# ProPrj.net
KiCad netlist of a schematic drawn in EasyEDA Pro
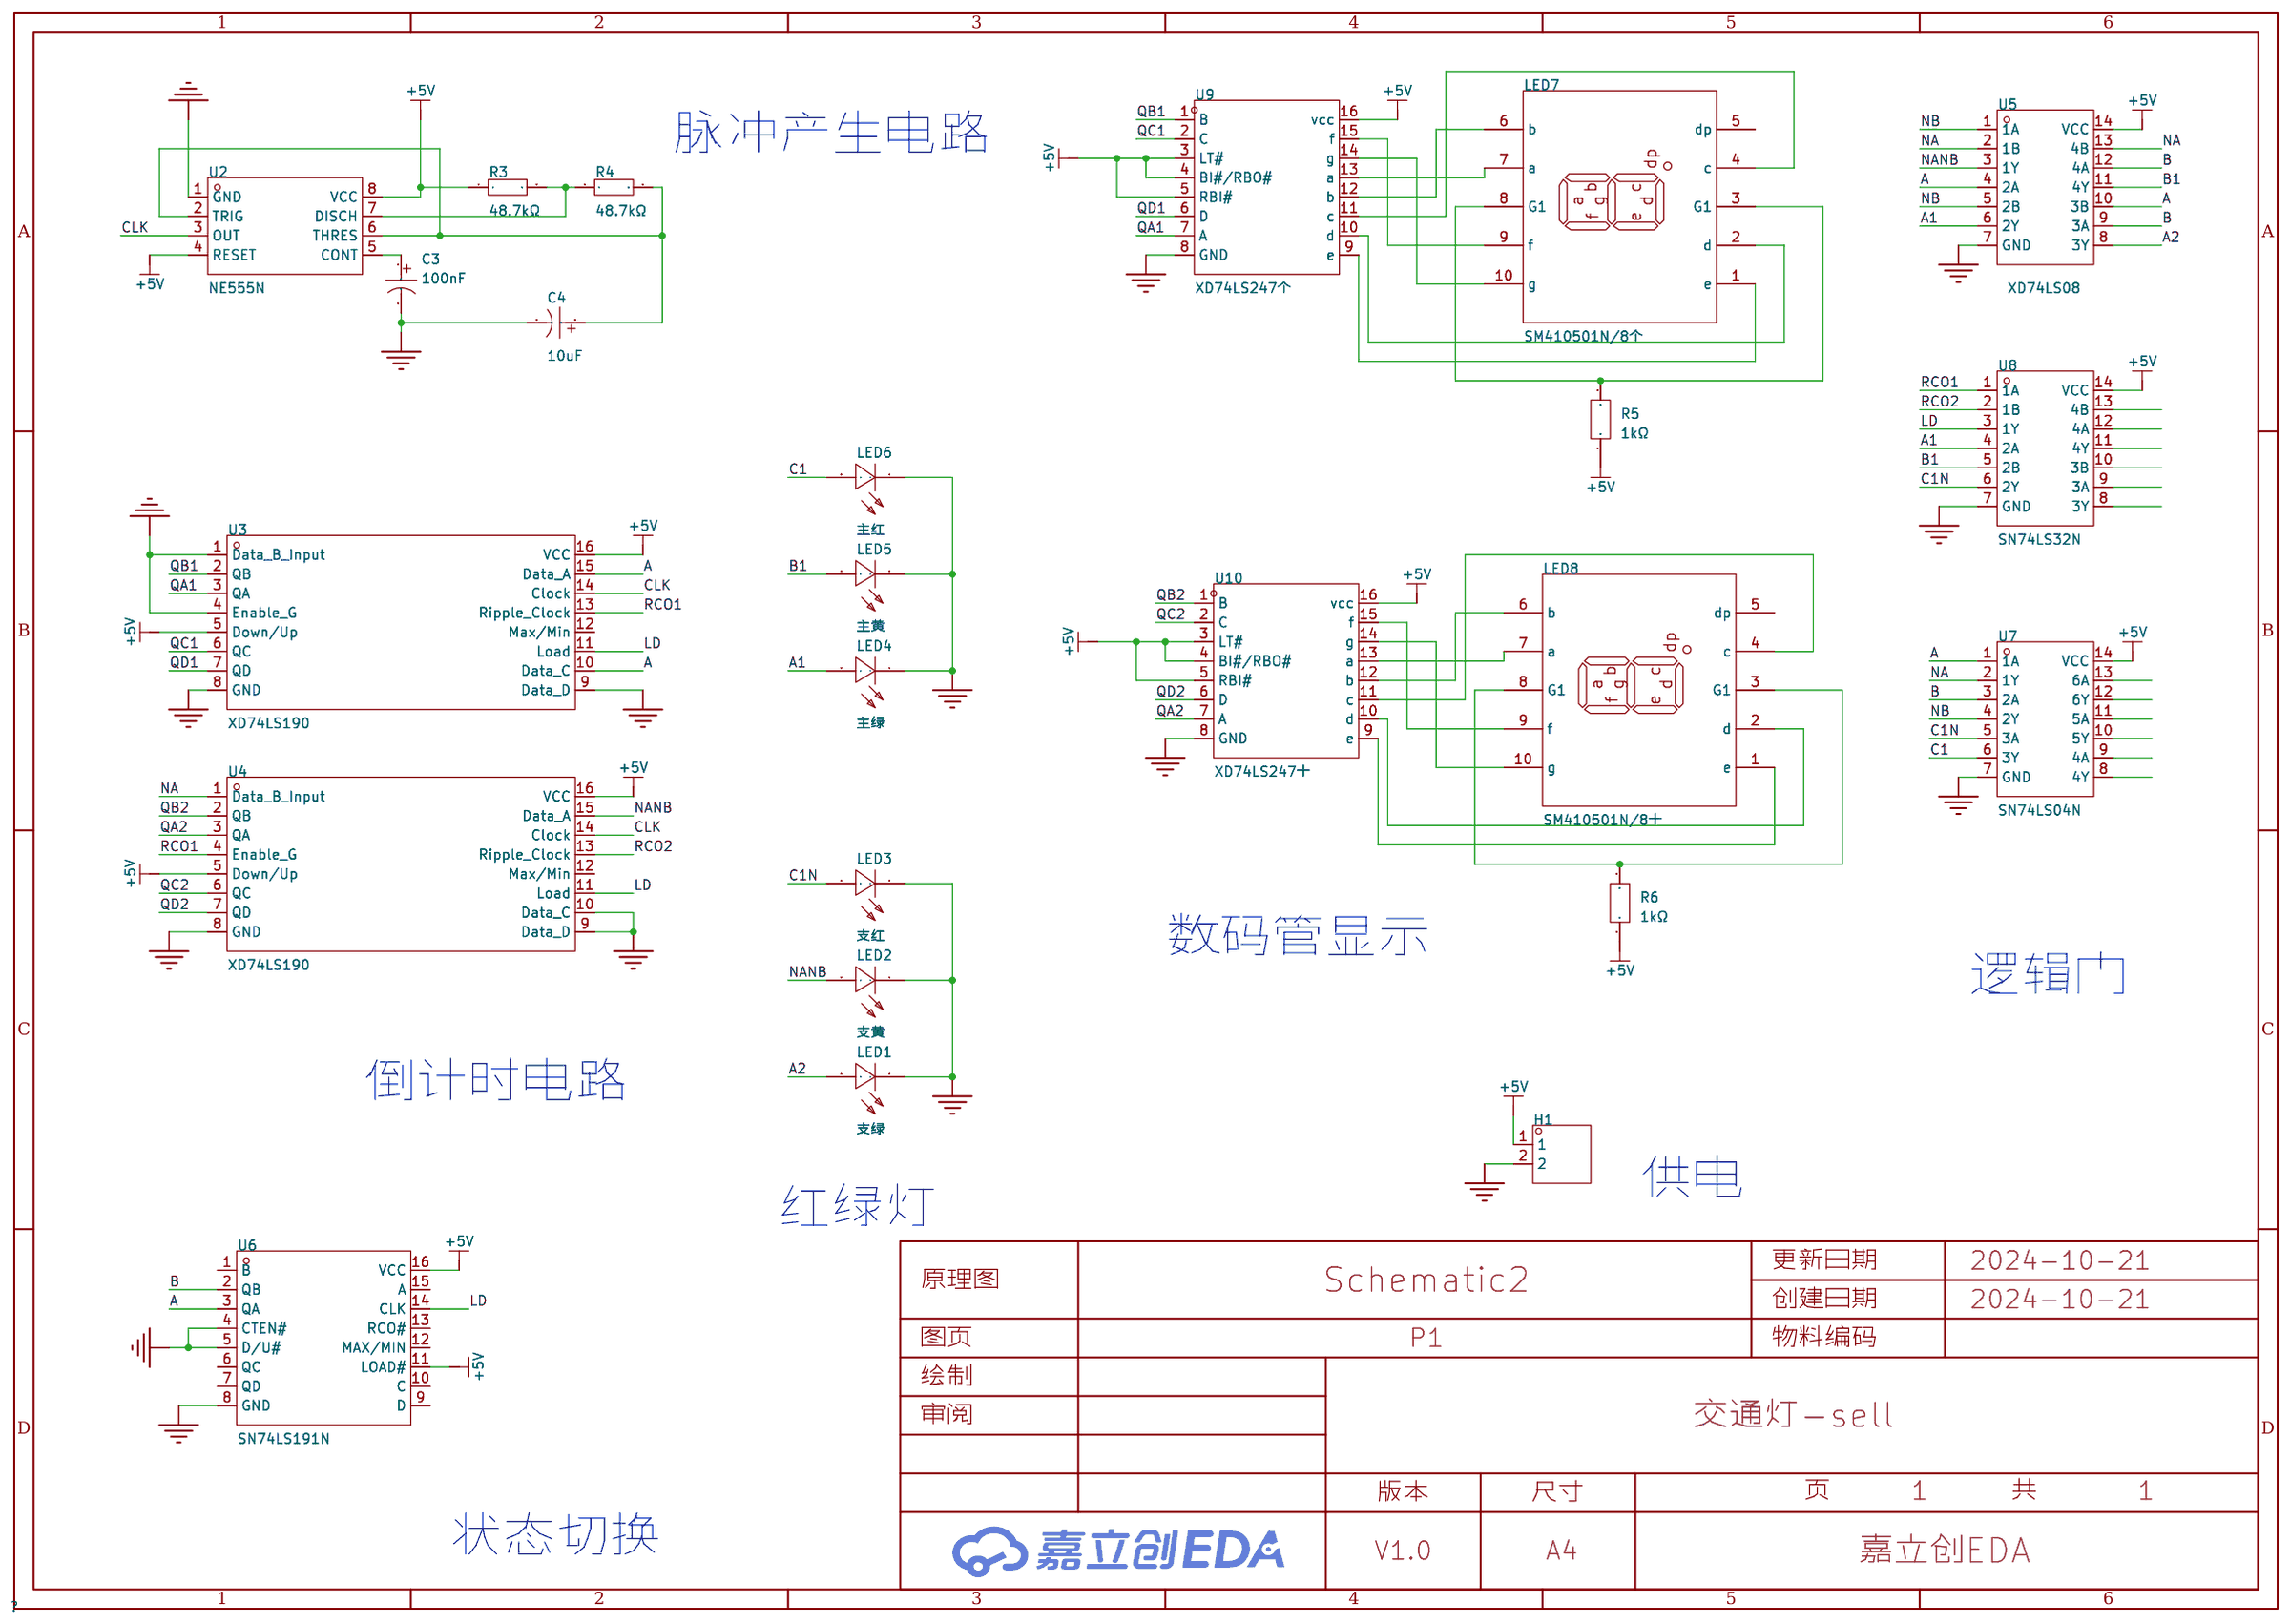
[diagram p0: schematic sheet]

(export (version "E")
  (design (tool "Eeschema 10.0.6"))
  (components
    (comp (ref "C3")
      (value "100nF")
      (footprint "easyedapro:CAP-TH_BD4.0-P1.50-D0.8-FD")
      (description "容值:100nF;精度:±20%;额定电压:50V;纹波电流:1A@100kHz;等效串联电阻:-;")
      (fields
        (field (name "Manufacturer Part") "KS104M050C07RR0VH2FP0")
        (field (name "Manufacturer") "CX(承兴)")
      )
      (libsource (lib "easyedapro") (part "0.1uF 50V 4*7"))
    )
    (comp (ref "C4")
      (value "10uF")
      (footprint "easyedapro:CAP-TH_BD5.0-P2.00-D0.8-FD")
      (description "容值:10uF;精度:±20%;额定电压:50V;")
      (fields (field (name "Manufacturer Part") "ERS1HM100D11OT") (field (name "Manufacturer") "AISHI(艾华集团)"))
      (libsource (lib "easyedapro") (part "ERS1HM100D11OT"))
    )
    (comp (ref "H1")
      (value "~")
      (footprint "easyedapro:HDR-TH_2P-P2.54-V-M-1")
      (libsource (lib "easyedapro") (part "210S-1*2P L=11.6MMGold-plated black"))
    )
    (comp (ref "LED1")
      (value "支绿")
      (footprint "easyedapro:LED-TH_BD3.9-P2.54-RD")
      (fields (field (name "Manufacturer") "EVERLIGHT(亿光)"))
      (libsource (lib "easyedapro") (part "204-10SUGD/S400-A4-L"))
    )
    (comp (ref "LED2")
      (value "支黄")
      (footprint "easyedapro:LED-TH_BD3.9-P2.54-RD")
      (fields (field (name "Manufacturer") "EVERLIGHT(亿光)"))
      (libsource (lib "easyedapro") (part "204-10SUGD/S400-A4-L"))
    )
    (comp (ref "LED3")
      (value "支红")
      (footprint "easyedapro:LED-TH_BD3.9-P2.54-RD")
      (fields (field (name "Manufacturer") "EVERLIGHT(亿光)"))
      (libsource (lib "easyedapro") (part "204-10SUGD/S400-A4-L"))
    )
    (comp (ref "LED4")
      (value "主绿")
      (footprint "easyedapro:LED-TH_BD3.9-P2.54-RD")
      (fields (field (name "Manufacturer") "EVERLIGHT(亿光)"))
      (libsource (lib "easyedapro") (part "204-10SUGD/S400-A4-L"))
    )
    (comp (ref "LED5")
      (value "主黄")
      (footprint "easyedapro:LED-TH_BD3.9-P2.54-RD")
      (fields (field (name "Manufacturer") "EVERLIGHT(亿光)"))
      (libsource (lib "easyedapro") (part "204-10SUGD/S400-A4-L"))
    )
    (comp (ref "LED6")
      (value "主红")
      (footprint "easyedapro:LED-TH_BD3.9-P2.54-RD")
      (fields (field (name "Manufacturer") "EVERLIGHT(亿光)"))
      (libsource (lib "easyedapro") (part "204-10SUGD/S400-A4-L"))
    )
    (comp (ref "LED7")
      (value "SM410501N/8个")
      (footprint "easyedapro:LED-SEG-TH_10P-L12.7-W19.0-P2.54-S15.24-BL")
      (description "数码管位数:1位;发光颜色:红色;LED极性:共阳极;数字/字母大小(英寸):0.5;")
      (fields (field (name "Manufacturer") "ARKLED(方舟)"))
      (libsource (lib "easyedapro") (part "SM410501N/8"))
    )
    (comp (ref "LED8")
      (value "SM410501N/8十")
      (footprint "easyedapro:LED-SEG-TH_10P-L12.7-W19.0-P2.54-S15.24-BL")
      (description "数码管位数:1位;发光颜色:红色;LED极性:共阳极;数字/字母大小(英寸):0.5;")
      (fields (field (name "Manufacturer") "ARKLED(方舟)"))
      (libsource (lib "easyedapro") (part "SM410501N/8"))
    )
    (comp (ref "R3")
      (value "48.7kΩ")
      (footprint "easyedapro:RES-TH_BD2.4-L6.3-P10.30-D0.6")
      (description "电阻类型:金属膜电阻;阻值:48.7kΩ;精度:±1%;功率:250mW;温度系数:±100ppm/°C;")
      (fields (field (name "Manufacturer Part") "MFR-25FBF52-48K7") (field (name "Manufacturer") "YAGEO(国巨)"))
      (libsource (lib "easyedapro") (part "MFR-25FBF52-48K7"))
    )
    (comp (ref "R4")
      (value "48.7kΩ")
      (footprint "easyedapro:RES-TH_BD2.4-L6.3-P10.30-D0.6")
      (description "电阻类型:金属膜电阻;阻值:48.7kΩ;精度:±1%;功率:250mW;温度系数:±100ppm/°C;")
      (fields (field (name "Manufacturer Part") "MFR-25FBF52-48K7") (field (name "Manufacturer") "YAGEO(国巨)"))
      (libsource (lib "easyedapro") (part "MFR-25FBF52-48K7"))
    )
    (comp (ref "R5")
      (value "1kΩ")
      (footprint "easyedapro:RES-TH_BD2.3-L6.5-P10.50-D0.5")
      (description "电阻类型:金属膜电阻;阻值:1kΩ;精度:±1%;功率:250mW;温度系数:±200ppm/°C;")
      (fields (field (name "Manufacturer Part") "MF1/4W-1KΩ±1%T52") (field (name "Manufacturer") "华星机电"))
      (libsource (lib "easyedapro") (part "MF1/4W-1KΩ±1%T52"))
    )
    (comp (ref "R6")
      (value "1kΩ")
      (footprint "easyedapro:RES-TH_BD2.3-L6.5-P10.50-D0.5")
      (description "电阻类型:金属膜电阻;阻值:1kΩ;精度:±1%;功率:250mW;温度系数:±200ppm/°C;")
      (fields (field (name "Manufacturer Part") "MF1/4W-1KΩ±1%T52") (field (name "Manufacturer") "华星机电"))
      (libsource (lib "easyedapro") (part "MF1/4W-1KΩ±1%T52"))
    )
    (comp (ref "U2")
      (value "NE555N")
      (footprint "easyedapro:DIP-8_L9.8-W6.6-P2.54-LS7.6-BL")
      (fields (field (name "Manufacturer") "HGSEMI(华冠)"))
      (libsource (lib "easyedapro") (part "NE555N"))
    )
    (comp (ref "U3")
      (value "XD74LS190")
      (footprint "easyedapro:DIP-16_L20.0-W6.4-P2.54-LS7.6-BL")
      (fields (field (name "Manufacturer") "XINLUDA(信路达)"))
      (libsource (lib "easyedapro") (part "XD74LS190"))
    )
    (comp (ref "U4")
      (value "XD74LS190")
      (footprint "easyedapro:DIP-16_L20.0-W6.4-P2.54-LS7.6-BL")
      (fields (field (name "Manufacturer") "XINLUDA(信路达)"))
      (libsource (lib "easyedapro") (part "XD74LS190"))
    )
    (comp (ref "U5")
      (value "XD74LS08")
      (footprint "easyedapro:DIP-14_L19.4-W6.4-P2.54-LS7.6-BL")
      (description "逻辑类型:-;")
      (fields (field (name "Manufacturer") "XINLUDA(信路达)"))
      (libsource (lib "easyedapro") (part "XD74LS08"))
    )
    (comp (ref "U6")
      (value "SN74LS191N")
      (footprint "easyedapro:PDIP-16_L19.3-W6.4-P2.54-LS7.94-BL")
      (description "工作电压:4.75V~5.25V;元件数:1;触发沿:上升沿;计数速率:25MHz;")
      (fields (field (name "Manufacturer") "TI(德州仪器)"))
      (libsource (lib "easyedapro") (part "SN74LS191N"))
    )
    (comp (ref "U7")
      (value "SN74LS04N")
      (footprint "easyedapro:DIP-14_L19.1-W6.4-P2.54-LS7.6-BL")
      (description "电源电压:2V~6V;供电电流(最大值):2uA;电路数:6;最大传播延迟(tpd):14ns@6V;")
      (fields (field (name "Manufacturer") "LX(灵星芯微)"))
      (libsource (lib "easyedapro") (part "sn74ls04n(lx)"))
    )
    (comp (ref "U8")
      (value "SN74LS32N")
      (footprint "easyedapro:DIP-14_L19.1-W6.4-P2.54-LS7.6-BL")
      (fields (field (name "Manufacturer") "LX(灵星芯微)"))
      (libsource (lib "easyedapro") (part "sn74ls32n_c22466295"))
    )
    (comp (ref "U9")
      (value "XD74LS247个")
      (footprint "easyedapro:DIP-16_L19.3-W6.4-P2.54-LS7.6-BL")
      (description "BCD 到 7 段解码器/驱动器")
      (fields (field (name "Manufacturer") "XINLUDA(信路达)"))
      (libsource (lib "easyedapro") (part "XD74LS247"))
    )
    (comp (ref "U10")
      (value "XD74LS247十")
      (footprint "easyedapro:DIP-16_L19.3-W6.4-P2.54-LS7.6-BL")
      (description "BCD 到 7 段解码器/驱动器")
      (fields (field (name "Manufacturer") "XINLUDA(信路达)"))
      (libsource (lib "easyedapro") (part "XD74LS247"))
    )
  )
  (nets
    (net (code "1") (name "+5V") (class "Default")
      (node (ref "H1") (pin "1") (pinfunction "1_1") (pintype "unspecified"))
      (node (ref "R3") (pin "1") (pinfunction "1_1") (pintype "unspecified"))
      (node (ref "R5") (pin "1") (pinfunction "1_1") (pintype "unspecified"))
      (node (ref "R6") (pin "1") (pinfunction "1_1") (pintype "unspecified"))
      (node (ref "U10") (pin "16") (pinfunction "vcc_16") (pintype "unspecified"))
      (node (ref "U10") (pin "3") (pinfunction "LT#_3") (pintype "unspecified"))
      (node (ref "U10") (pin "4") (pinfunction "BI#/RBO#_4") (pintype "unspecified"))
      (node (ref "U10") (pin "5") (pinfunction "RBI#_5") (pintype "unspecified"))
      (node (ref "U2") (pin "4") (pinfunction "RESET_4") (pintype "unspecified"))
      (node (ref "U2") (pin "8") (pinfunction "VCC_8") (pintype "unspecified"))
      (node (ref "U3") (pin "16") (pinfunction "VCC_16") (pintype "unspecified"))
      (node (ref "U3") (pin "5") (pinfunction "Down/Up_5") (pintype "unspecified"))
      (node (ref "U4") (pin "16") (pinfunction "VCC_16") (pintype "unspecified"))
      (node (ref "U4") (pin "5") (pinfunction "Down/Up_5") (pintype "unspecified"))
      (node (ref "U5") (pin "14") (pinfunction "VCC_14") (pintype "input"))
      (node (ref "U6") (pin "11") (pinfunction "LOAD#_11") (pintype "unspecified"))
      (node (ref "U6") (pin "16") (pinfunction "VCC_16") (pintype "unspecified"))
      (node (ref "U7") (pin "14") (pinfunction "VCC_14") (pintype "unspecified"))
      (node (ref "U8") (pin "14") (pinfunction "VCC_14") (pintype "unspecified"))
      (node (ref "U9") (pin "16") (pinfunction "vcc_16") (pintype "unspecified"))
      (node (ref "U9") (pin "3") (pinfunction "LT#_3") (pintype "unspecified"))
      (node (ref "U9") (pin "4") (pinfunction "BI#/RBO#_4") (pintype "unspecified"))
      (node (ref "U9") (pin "5") (pinfunction "RBI#_5") (pintype "unspecified"))
    )
    (net (code "2") (name "/A") (class "Default")
      (node (ref "U3") (pin "10") (pinfunction "Data_C_10") (pintype "unspecified"))
      (node (ref "U3") (pin "15") (pinfunction "Data_A_15") (pintype "unspecified"))
      (node (ref "U5") (pin "10") (pinfunction "3B_10") (pintype "input"))
      (node (ref "U5") (pin "4") (pinfunction "2A_4") (pintype "input"))
      (node (ref "U6") (pin "3") (pinfunction "QA_3") (pintype "unspecified"))
      (node (ref "U7") (pin "1") (pinfunction "1A_1") (pintype "unspecified"))
    )
    (net (code "3") (name "/A1") (class "Default")
      (node (ref "LED4") (pin "2") (pinfunction "+_2") (pintype "input"))
      (node (ref "U5") (pin "6") (pinfunction "2Y_6") (pintype "input"))
      (node (ref "U8") (pin "4") (pinfunction "2A_4") (pintype "unspecified"))
    )
    (net (code "4") (name "/A2") (class "Default")
      (node (ref "LED1") (pin "2") (pinfunction "+_2") (pintype "input"))
      (node (ref "U5") (pin "8") (pinfunction "3Y_8") (pintype "input"))
    )
    (net (code "5") (name "/B") (class "Default")
      (node (ref "U5") (pin "12") (pinfunction "4A_12") (pintype "input"))
      (node (ref "U5") (pin "9") (pinfunction "3A_9") (pintype "input"))
      (node (ref "U6") (pin "2") (pinfunction "QB_2") (pintype "unspecified"))
      (node (ref "U7") (pin "3") (pinfunction "2A_3") (pintype "unspecified"))
    )
    (net (code "6") (name "/B1") (class "Default")
      (node (ref "LED5") (pin "2") (pinfunction "+_2") (pintype "input"))
      (node (ref "U5") (pin "11") (pinfunction "4Y_11") (pintype "input"))
      (node (ref "U8") (pin "5") (pinfunction "2B_5") (pintype "unspecified"))
    )
    (net (code "7") (name "/C1") (class "Default")
      (node (ref "LED6") (pin "2") (pinfunction "+_2") (pintype "input"))
      (node (ref "U7") (pin "6") (pinfunction "3Y_6") (pintype "unspecified"))
    )
    (net (code "8") (name "/C1N") (class "Default")
      (node (ref "LED3") (pin "2") (pinfunction "+_2") (pintype "input"))
      (node (ref "U7") (pin "5") (pinfunction "3A_5") (pintype "unspecified"))
      (node (ref "U8") (pin "6") (pinfunction "2Y_6") (pintype "unspecified"))
    )
    (net (code "9") (name "/CLK") (class "Default")
      (node (ref "U2") (pin "3") (pinfunction "OUT_3") (pintype "unspecified"))
      (node (ref "U3") (pin "14") (pinfunction "Clock_14") (pintype "unspecified"))
      (node (ref "U4") (pin "14") (pinfunction "Clock_14") (pintype "unspecified"))
    )
    (net (code "10") (name "/LD") (class "Default")
      (node (ref "U3") (pin "11") (pinfunction "Load_11") (pintype "unspecified"))
      (node (ref "U4") (pin "11") (pinfunction "Load_11") (pintype "unspecified"))
      (node (ref "U6") (pin "14") (pinfunction "CLK_14") (pintype "unspecified"))
      (node (ref "U8") (pin "3") (pinfunction "1Y_3") (pintype "unspecified"))
    )
    (net (code "11") (name "/NA") (class "Default")
      (node (ref "U4") (pin "1") (pinfunction "Data_B_Input_1") (pintype "unspecified"))
      (node (ref "U5") (pin "13") (pinfunction "4B_13") (pintype "input"))
      (node (ref "U5") (pin "2") (pinfunction "1B_2") (pintype "input"))
      (node (ref "U7") (pin "2") (pinfunction "1Y_2") (pintype "unspecified"))
    )
    (net (code "12") (name "/NANB") (class "Default")
      (node (ref "LED2") (pin "2") (pinfunction "+_2") (pintype "input"))
      (node (ref "U4") (pin "15") (pinfunction "Data_A_15") (pintype "unspecified"))
      (node (ref "U5") (pin "3") (pinfunction "1Y_3") (pintype "input"))
    )
    (net (code "13") (name "/NB") (class "Default")
      (node (ref "U5") (pin "1") (pinfunction "1A_1") (pintype "input"))
      (node (ref "U5") (pin "5") (pinfunction "2B_5") (pintype "input"))
      (node (ref "U7") (pin "4") (pinfunction "2Y_4") (pintype "unspecified"))
    )
    (net (code "14") (name "/QA1") (class "Default")
      (node (ref "U3") (pin "3") (pinfunction "QA_3") (pintype "unspecified"))
      (node (ref "U9") (pin "7") (pinfunction "A_7") (pintype "unspecified"))
    )
    (net (code "15") (name "/QA2") (class "Default")
      (node (ref "U10") (pin "7") (pinfunction "A_7") (pintype "unspecified"))
      (node (ref "U4") (pin "3") (pinfunction "QA_3") (pintype "unspecified"))
    )
    (net (code "16") (name "/QB1") (class "Default")
      (node (ref "U3") (pin "2") (pinfunction "QB_2") (pintype "unspecified"))
      (node (ref "U9") (pin "1") (pinfunction "B_1") (pintype "unspecified"))
    )
    (net (code "17") (name "/QB2") (class "Default")
      (node (ref "U10") (pin "1") (pinfunction "B_1") (pintype "unspecified"))
      (node (ref "U4") (pin "2") (pinfunction "QB_2") (pintype "unspecified"))
    )
    (net (code "18") (name "/QC1") (class "Default")
      (node (ref "U3") (pin "6") (pinfunction "QC_6") (pintype "unspecified"))
      (node (ref "U9") (pin "2") (pinfunction "C_2") (pintype "unspecified"))
    )
    (net (code "19") (name "/QC2") (class "Default")
      (node (ref "U10") (pin "2") (pinfunction "C_2") (pintype "unspecified"))
      (node (ref "U4") (pin "6") (pinfunction "QC_6") (pintype "unspecified"))
    )
    (net (code "20") (name "/QD1") (class "Default")
      (node (ref "U3") (pin "7") (pinfunction "QD_7") (pintype "unspecified"))
      (node (ref "U9") (pin "6") (pinfunction "D_6") (pintype "unspecified"))
    )
    (net (code "21") (name "/QD2") (class "Default")
      (node (ref "U10") (pin "6") (pinfunction "D_6") (pintype "unspecified"))
      (node (ref "U4") (pin "7") (pinfunction "QD_7") (pintype "unspecified"))
    )
    (net (code "22") (name "/RCO1") (class "Default")
      (node (ref "U3") (pin "13") (pinfunction "Ripple_Clock_13") (pintype "unspecified"))
      (node (ref "U4") (pin "4") (pinfunction "Enable_G_4") (pintype "unspecified"))
      (node (ref "U8") (pin "1") (pinfunction "1A_1") (pintype "unspecified"))
    )
    (net (code "23") (name "/RCO2") (class "Default")
      (node (ref "U4") (pin "13") (pinfunction "Ripple_Clock_13") (pintype "unspecified"))
      (node (ref "U8") (pin "2") (pinfunction "1B_2") (pintype "unspecified"))
    )
    (net (code "24") (name "GND") (class "Default")
      (node (ref "C3") (pin "2") (pinfunction "2_2") (pintype "input"))
      (node (ref "C4") (pin "2") (pinfunction "2_2") (pintype "input"))
      (node (ref "H1") (pin "2") (pinfunction "2_2") (pintype "unspecified"))
      (node (ref "LED1") (pin "1") (pinfunction "-_1") (pintype "input"))
      (node (ref "LED2") (pin "1") (pinfunction "-_1") (pintype "input"))
      (node (ref "LED3") (pin "1") (pinfunction "-_1") (pintype "input"))
      (node (ref "LED4") (pin "1") (pinfunction "-_1") (pintype "input"))
      (node (ref "LED5") (pin "1") (pinfunction "-_1") (pintype "input"))
      (node (ref "LED6") (pin "1") (pinfunction "-_1") (pintype "input"))
      (node (ref "U10") (pin "8") (pinfunction "GND_8") (pintype "unspecified"))
      (node (ref "U2") (pin "1") (pinfunction "GND_1") (pintype "unspecified"))
      (node (ref "U3") (pin "1") (pinfunction "Data_B_Input_1") (pintype "unspecified"))
      (node (ref "U3") (pin "4") (pinfunction "Enable_G_4") (pintype "unspecified"))
      (node (ref "U3") (pin "8") (pinfunction "GND_8") (pintype "unspecified"))
      (node (ref "U3") (pin "9") (pinfunction "Data_D_9") (pintype "unspecified"))
      (node (ref "U4") (pin "10") (pinfunction "Data_C_10") (pintype "unspecified"))
      (node (ref "U4") (pin "8") (pinfunction "GND_8") (pintype "unspecified"))
      (node (ref "U4") (pin "9") (pinfunction "Data_D_9") (pintype "unspecified"))
      (node (ref "U5") (pin "7") (pinfunction "GND_7") (pintype "input"))
      (node (ref "U6") (pin "4") (pinfunction "CTEN#_4") (pintype "unspecified"))
      (node (ref "U6") (pin "5") (pinfunction "D/U#_5") (pintype "unspecified"))
      (node (ref "U6") (pin "8") (pinfunction "GND_8") (pintype "unspecified"))
      (node (ref "U7") (pin "7") (pinfunction "GND_7") (pintype "unspecified"))
      (node (ref "U8") (pin "7") (pinfunction "GND_7") (pintype "unspecified"))
      (node (ref "U9") (pin "8") (pinfunction "GND_8") (pintype "unspecified"))
    )
    (net (code "25") (name "Net-(LED7-G1-Pad3)") (class "Default")
      (node (ref "LED7") (pin "3") (pinfunction "G1_3") (pintype "input"))
      (node (ref "LED7") (pin "8") (pinfunction "G1_8") (pintype "input"))
      (node (ref "R5") (pin "2") (pinfunction "2_2") (pintype "unspecified"))
    )
    (net (code "26") (name "Net-(LED7-a)") (class "Default")
      (node (ref "LED7") (pin "7") (pinfunction "a_7") (pintype "input"))
      (node (ref "U9") (pin "13") (pinfunction "a_13") (pintype "unspecified"))
    )
    (net (code "27") (name "Net-(LED7-b)") (class "Default")
      (node (ref "LED7") (pin "6") (pinfunction "b_6") (pintype "input"))
      (node (ref "U9") (pin "12") (pinfunction "b_12") (pintype "unspecified"))
    )
    (net (code "28") (name "Net-(LED7-c)") (class "Default")
      (node (ref "LED7") (pin "4") (pinfunction "c_4") (pintype "input"))
      (node (ref "U9") (pin "11") (pinfunction "c_11") (pintype "unspecified"))
    )
    (net (code "29") (name "Net-(LED7-d)") (class "Default")
      (node (ref "LED7") (pin "2") (pinfunction "d_2") (pintype "input"))
      (node (ref "U9") (pin "10") (pinfunction "d_10") (pintype "unspecified"))
    )
    (net (code "30") (name "Net-(LED7-e)") (class "Default")
      (node (ref "LED7") (pin "1") (pinfunction "e_1") (pintype "input"))
      (node (ref "U9") (pin "9") (pinfunction "e_9") (pintype "unspecified"))
    )
    (net (code "31") (name "Net-(LED7-f)") (class "Default")
      (node (ref "LED7") (pin "9") (pinfunction "f_9") (pintype "input"))
      (node (ref "U9") (pin "15") (pinfunction "f_15") (pintype "unspecified"))
    )
    (net (code "32") (name "Net-(LED7-g)") (class "Default")
      (node (ref "LED7") (pin "10") (pinfunction "g_10") (pintype "input"))
      (node (ref "U9") (pin "14") (pinfunction "g_14") (pintype "unspecified"))
    )
    (net (code "33") (name "Net-(LED8-G1-Pad3)") (class "Default")
      (node (ref "LED8") (pin "3") (pinfunction "G1_3") (pintype "input"))
      (node (ref "LED8") (pin "8") (pinfunction "G1_8") (pintype "input"))
      (node (ref "R6") (pin "2") (pinfunction "2_2") (pintype "unspecified"))
    )
    (net (code "34") (name "Net-(LED8-a)") (class "Default")
      (node (ref "LED8") (pin "7") (pinfunction "a_7") (pintype "input"))
      (node (ref "U10") (pin "13") (pinfunction "a_13") (pintype "unspecified"))
    )
    (net (code "35") (name "Net-(LED8-b)") (class "Default")
      (node (ref "LED8") (pin "6") (pinfunction "b_6") (pintype "input"))
      (node (ref "U10") (pin "12") (pinfunction "b_12") (pintype "unspecified"))
    )
    (net (code "36") (name "Net-(LED8-c)") (class "Default")
      (node (ref "LED8") (pin "4") (pinfunction "c_4") (pintype "input"))
      (node (ref "U10") (pin "11") (pinfunction "c_11") (pintype "unspecified"))
    )
    (net (code "37") (name "Net-(LED8-d)") (class "Default")
      (node (ref "LED8") (pin "2") (pinfunction "d_2") (pintype "input"))
      (node (ref "U10") (pin "10") (pinfunction "d_10") (pintype "unspecified"))
    )
    (net (code "38") (name "Net-(LED8-e)") (class "Default")
      (node (ref "LED8") (pin "1") (pinfunction "e_1") (pintype "input"))
      (node (ref "U10") (pin "9") (pinfunction "e_9") (pintype "unspecified"))
    )
    (net (code "39") (name "Net-(LED8-f)") (class "Default")
      (node (ref "LED8") (pin "9") (pinfunction "f_9") (pintype "input"))
      (node (ref "U10") (pin "15") (pinfunction "f_15") (pintype "unspecified"))
    )
    (net (code "40") (name "Net-(LED8-g)") (class "Default")
      (node (ref "LED8") (pin "10") (pinfunction "g_10") (pintype "input"))
      (node (ref "U10") (pin "14") (pinfunction "g_14") (pintype "unspecified"))
    )
    (net (code "41") (name "Net-(U2-CONT)") (class "Default")
      (node (ref "C3") (pin "1") (pinfunction "1_1") (pintype "input"))
      (node (ref "U2") (pin "5") (pinfunction "CONT_5") (pintype "unspecified"))
    )
    (net (code "42") (name "Net-(U2-DISCH)") (class "Default")
      (node (ref "R3") (pin "2") (pinfunction "2_2") (pintype "unspecified"))
      (node (ref "R4") (pin "1") (pinfunction "1_1") (pintype "unspecified"))
      (node (ref "U2") (pin "7") (pinfunction "DISCH_7") (pintype "unspecified"))
    )
    (net (code "43") (name "Net-(U2-THRES)") (class "Default")
      (node (ref "C4") (pin "1") (pinfunction "1_1") (pintype "input"))
      (node (ref "R4") (pin "2") (pinfunction "2_2") (pintype "unspecified"))
      (node (ref "U2") (pin "2") (pinfunction "TRIG_2") (pintype "unspecified"))
      (node (ref "U2") (pin "6") (pinfunction "THRES_6") (pintype "unspecified"))
    )
    (net (code "44") (name "unconnected-(LED7-dp-Pad5)") (class "Default")
      (node (ref "LED7") (pin "5") (pinfunction "dp_5") (pintype "input"))
    )
    (net (code "45") (name "unconnected-(LED8-dp-Pad5)") (class "Default")
      (node (ref "LED8") (pin "5") (pinfunction "dp_5") (pintype "input"))
    )
    (net (code "46") (name "unconnected-(U3-Max{slash}Min-Pad12)") (class "Default")
      (node (ref "U3") (pin "12") (pinfunction "Max/Min_12") (pintype "unspecified"))
    )
    (net (code "47") (name "unconnected-(U4-Max{slash}Min-Pad12)") (class "Default")
      (node (ref "U4") (pin "12") (pinfunction "Max/Min_12") (pintype "unspecified"))
    )
    (net (code "48") (name "unconnected-(U6-A-Pad15)") (class "Default")
      (node (ref "U6") (pin "15") (pinfunction "A_15") (pintype "unspecified"))
    )
    (net (code "49") (name "unconnected-(U6-B-Pad1)") (class "Default")
      (node (ref "U6") (pin "1") (pinfunction "B_1") (pintype "unspecified"))
    )
    (net (code "50") (name "unconnected-(U6-C-Pad10)") (class "Default")
      (node (ref "U6") (pin "10") (pinfunction "C_10") (pintype "unspecified"))
    )
    (net (code "51") (name "unconnected-(U6-D-Pad9)") (class "Default")
      (node (ref "U6") (pin "9") (pinfunction "D_9") (pintype "unspecified"))
    )
    (net (code "52") (name "unconnected-(U6-MAX{slash}MIN-Pad12)") (class "Default")
      (node (ref "U6") (pin "12") (pinfunction "MAX/MIN_12") (pintype "unspecified"))
    )
    (net (code "53") (name "unconnected-(U6-QC-Pad6)") (class "Default")
      (node (ref "U6") (pin "6") (pinfunction "QC_6") (pintype "unspecified"))
    )
    (net (code "54") (name "unconnected-(U6-QD-Pad7)") (class "Default")
      (node (ref "U6") (pin "7") (pinfunction "QD_7") (pintype "unspecified"))
    )
    (net (code "55") (name "unconnected-(U6-RCO#-Pad13)") (class "Default")
      (node (ref "U6") (pin "13") (pinfunction "RCO#_13") (pintype "unspecified"))
    )
    (net (code "56") (name "unconnected-(U7-4A-Pad9)") (class "Default")
      (node (ref "U7") (pin "9") (pinfunction "4A_9") (pintype "unspecified"))
    )
    (net (code "57") (name "unconnected-(U7-4Y-Pad8)") (class "Default")
      (node (ref "U7") (pin "8") (pinfunction "4Y_8") (pintype "unspecified"))
    )
    (net (code "58") (name "unconnected-(U7-5A-Pad11)") (class "Default")
      (node (ref "U7") (pin "11") (pinfunction "5A_11") (pintype "unspecified"))
    )
    (net (code "59") (name "unconnected-(U7-5Y-Pad10)") (class "Default")
      (node (ref "U7") (pin "10") (pinfunction "5Y_10") (pintype "unspecified"))
    )
    (net (code "60") (name "unconnected-(U7-6A-Pad13)") (class "Default")
      (node (ref "U7") (pin "13") (pinfunction "6A_13") (pintype "unspecified"))
    )
    (net (code "61") (name "unconnected-(U7-6Y-Pad12)") (class "Default")
      (node (ref "U7") (pin "12") (pinfunction "6Y_12") (pintype "unspecified"))
    )
    (net (code "62") (name "unconnected-(U8-3A-Pad9)") (class "Default")
      (node (ref "U8") (pin "9") (pinfunction "3A_9") (pintype "unspecified"))
    )
    (net (code "63") (name "unconnected-(U8-3B-Pad10)") (class "Default")
      (node (ref "U8") (pin "10") (pinfunction "3B_10") (pintype "unspecified"))
    )
    (net (code "64") (name "unconnected-(U8-3Y-Pad8)") (class "Default")
      (node (ref "U8") (pin "8") (pinfunction "3Y_8") (pintype "unspecified"))
    )
    (net (code "65") (name "unconnected-(U8-4A-Pad12)") (class "Default")
      (node (ref "U8") (pin "12") (pinfunction "4A_12") (pintype "unspecified"))
    )
    (net (code "66") (name "unconnected-(U8-4B-Pad13)") (class "Default")
      (node (ref "U8") (pin "13") (pinfunction "4B_13") (pintype "unspecified"))
    )
    (net (code "67") (name "unconnected-(U8-4Y-Pad11)") (class "Default")
      (node (ref "U8") (pin "11") (pinfunction "4Y_11") (pintype "unspecified"))
    )
  )
)
